# drone_encorder.net
KiCad netlist of a schematic drawn in EAGLE
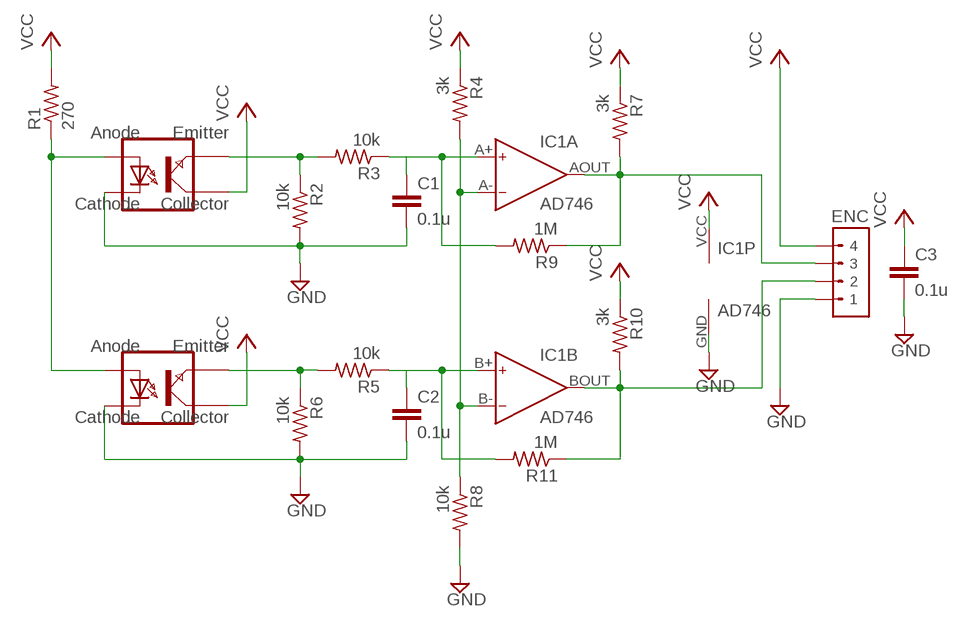
[diagram p0: schematic, sheet 1]

(export (version "E")
  (design (tool "Eeschema 10.0.6"))
  (components
    (comp (ref "C1")
      (value "0.1u")
      (footprint "eagle-import:C0603")
      (libsource (lib "eagle-import") (part "C-EUC0603"))
    )
    (comp (ref "C2")
      (value "0.1u")
      (footprint "eagle-import:C0603")
      (libsource (lib "eagle-import") (part "C-EUC0603"))
    )
    (comp (ref "C3")
      (value "0.1u")
      (footprint "eagle-import:C0603")
      (libsource (lib "eagle-import") (part "C-EUC0603"))
    )
    (comp (ref "ENC")
      (value "TOP_TYPE_4PIN")
      (footprint "eagle-import:TOP_TYPE_4PIN")
      (libsource (lib "eagle-import") (part "TOP_TYPE_4PIN"))
    )
    (comp (ref "IC1")
      (value "AD746")
      (footprint "eagle-import:NJM2903E")
      (libsource (lib "eagle-import") (part "AD746"))
    )
    (comp (ref "R1")
      (value "270")
      (footprint "eagle-import:R0603")
      (libsource (lib "eagle-import") (part "R-US_R0603"))
    )
    (comp (ref "R2")
      (value "10k")
      (footprint "eagle-import:R0603")
      (libsource (lib "eagle-import") (part "R-US_R0603"))
    )
    (comp (ref "R3")
      (value "10k")
      (footprint "eagle-import:R0603")
      (libsource (lib "eagle-import") (part "R-US_R0603"))
    )
    (comp (ref "R4")
      (value "3k")
      (footprint "eagle-import:R0603")
      (libsource (lib "eagle-import") (part "R-US_R0603"))
    )
    (comp (ref "R5")
      (value "10k")
      (footprint "eagle-import:R0603")
      (libsource (lib "eagle-import") (part "R-US_R0603"))
    )
    (comp (ref "R6")
      (value "10k")
      (footprint "eagle-import:R0603")
      (libsource (lib "eagle-import") (part "R-US_R0603"))
    )
    (comp (ref "R7")
      (value "3k")
      (footprint "eagle-import:R0603")
      (libsource (lib "eagle-import") (part "R-US_R0603"))
    )
    (comp (ref "R8")
      (value "10k")
      (footprint "eagle-import:R0603")
      (libsource (lib "eagle-import") (part "R-US_R0603"))
    )
    (comp (ref "R9")
      (value "1M")
      (footprint "eagle-import:R0603")
      (libsource (lib "eagle-import") (part "R-US_R0603"))
    )
    (comp (ref "R10")
      (value "3k")
      (footprint "eagle-import:R0603")
      (libsource (lib "eagle-import") (part "R-US_R0603"))
    )
    (comp (ref "R11")
      (value "1M")
      (footprint "eagle-import:R0603")
      (libsource (lib "eagle-import") (part "R-US_R0603"))
    )
    (comp (ref "U$1")
      (value "TPR-105F")
      (footprint "eagle-import:TPR-105F")
      (libsource (lib "eagle-import") (part "TPR-105F"))
    )
    (comp (ref "U$4")
      (value "TPR-105F")
      (footprint "eagle-import:TPR-105F")
      (libsource (lib "eagle-import") (part "TPR-105F"))
    )
  )
  (nets
    (net (code "1") (name "GND") (class "Default")
      (node (ref "C1") (pin "2") (pinfunction "2_2") (pintype "passive"))
      (node (ref "C2") (pin "2") (pinfunction "2_2") (pintype "passive"))
      (node (ref "C3") (pin "2") (pinfunction "2_2") (pintype "passive"))
      (node (ref "ENC") (pin "1") (pinfunction "1_1") (pintype "passive"))
      (node (ref "IC1") (pin "GND") (pinfunction "V-_GND") (pintype "power_in"))
      (node (ref "R2") (pin "2") (pinfunction "2_2") (pintype "passive"))
      (node (ref "R6") (pin "2") (pinfunction "2_2") (pintype "passive"))
      (node (ref "R8") (pin "2") (pinfunction "2_2") (pintype "passive"))
      (node (ref "U$1") (pin "CATHODE") (pinfunction "CATHODE_CATHODE") (pintype "bidirectional"))
      (node (ref "U$4") (pin "CATHODE") (pinfunction "CATHODE_CATHODE") (pintype "bidirectional"))
    )
    (net (code "2") (name "Net-(IC1A-IN+)") (class "Default")
      (node (ref "C1") (pin "1") (pinfunction "1_1") (pintype "passive"))
      (node (ref "IC1") (pin "A+") (pinfunction "IN+_A+") (pintype "input"))
      (node (ref "R3") (pin "1") (pinfunction "1_1") (pintype "passive"))
      (node (ref "R9") (pin "2") (pinfunction "2_2") (pintype "passive"))
    )
    (net (code "3") (name "Net-(IC1A-IN-)") (class "Default")
      (node (ref "IC1") (pin "A-") (pinfunction "IN-_A-") (pintype "input"))
      (node (ref "IC1") (pin "B-") (pinfunction "IN-_B-") (pintype "input"))
      (node (ref "R4") (pin "2") (pinfunction "2_2") (pintype "passive"))
      (node (ref "R8") (pin "1") (pinfunction "1_1") (pintype "passive"))
    )
    (net (code "4") (name "Net-(IC1A-OUT)") (class "Default")
      (node (ref "ENC") (pin "3") (pinfunction "3_3") (pintype "passive"))
      (node (ref "IC1") (pin "AOUT") (pinfunction "OUT_AOUT") (pintype "output"))
      (node (ref "R7") (pin "2") (pinfunction "2_2") (pintype "passive"))
      (node (ref "R9") (pin "1") (pinfunction "1_1") (pintype "passive"))
    )
    (net (code "5") (name "Net-(IC1B-IN+)") (class "Default")
      (node (ref "C2") (pin "1") (pinfunction "1_1") (pintype "passive"))
      (node (ref "IC1") (pin "B+") (pinfunction "IN+_B+") (pintype "input"))
      (node (ref "R11") (pin "2") (pinfunction "2_2") (pintype "passive"))
      (node (ref "R5") (pin "1") (pinfunction "1_1") (pintype "passive"))
    )
    (net (code "6") (name "Net-(IC1B-OUT)") (class "Default")
      (node (ref "ENC") (pin "2") (pinfunction "2_2") (pintype "passive"))
      (node (ref "IC1") (pin "BOUT") (pinfunction "OUT_BOUT") (pintype "output"))
      (node (ref "R10") (pin "2") (pinfunction "2_2") (pintype "passive"))
      (node (ref "R11") (pin "1") (pinfunction "1_1") (pintype "passive"))
    )
    (net (code "7") (name "Net-(R1-Pad1)") (class "Default")
      (node (ref "R1") (pin "1") (pinfunction "1_1") (pintype "passive"))
      (node (ref "U$1") (pin "ANODE") (pinfunction "ANODE_ANODE") (pintype "bidirectional"))
      (node (ref "U$4") (pin "ANODE") (pinfunction "ANODE_ANODE") (pintype "bidirectional"))
    )
    (net (code "8") (name "Net-(R2-Pad1)") (class "Default")
      (node (ref "R2") (pin "1") (pinfunction "1_1") (pintype "passive"))
      (node (ref "R3") (pin "2") (pinfunction "2_2") (pintype "passive"))
      (node (ref "U$4") (pin "EMITTER") (pinfunction "EMITTER_EMITTER") (pintype "bidirectional"))
    )
    (net (code "9") (name "Net-(R5-Pad2)") (class "Default")
      (node (ref "R5") (pin "2") (pinfunction "2_2") (pintype "passive"))
      (node (ref "R6") (pin "1") (pinfunction "1_1") (pintype "passive"))
      (node (ref "U$1") (pin "EMITTER") (pinfunction "EMITTER_EMITTER") (pintype "bidirectional"))
    )
    (net (code "10") (name "VCC") (class "Default")
      (node (ref "C3") (pin "1") (pinfunction "1_1") (pintype "passive"))
      (node (ref "ENC") (pin "4") (pinfunction "4_4") (pintype "passive"))
      (node (ref "IC1") (pin "VCC") (pinfunction "V+_VCC") (pintype "power_in"))
      (node (ref "R1") (pin "2") (pinfunction "2_2") (pintype "passive"))
      (node (ref "R10") (pin "1") (pinfunction "1_1") (pintype "passive"))
      (node (ref "R4") (pin "1") (pinfunction "1_1") (pintype "passive"))
      (node (ref "R7") (pin "1") (pinfunction "1_1") (pintype "passive"))
      (node (ref "U$1") (pin "COLLECTOR") (pinfunction "COLLECTOR_COLLECTOR") (pintype "bidirectional"))
      (node (ref "U$4") (pin "COLLECTOR") (pinfunction "COLLECTOR_COLLECTOR") (pintype "bidirectional"))
    )
  )
)
